# openTPM-v37.net
KiCad netlist of a schematic drawn in EAGLE
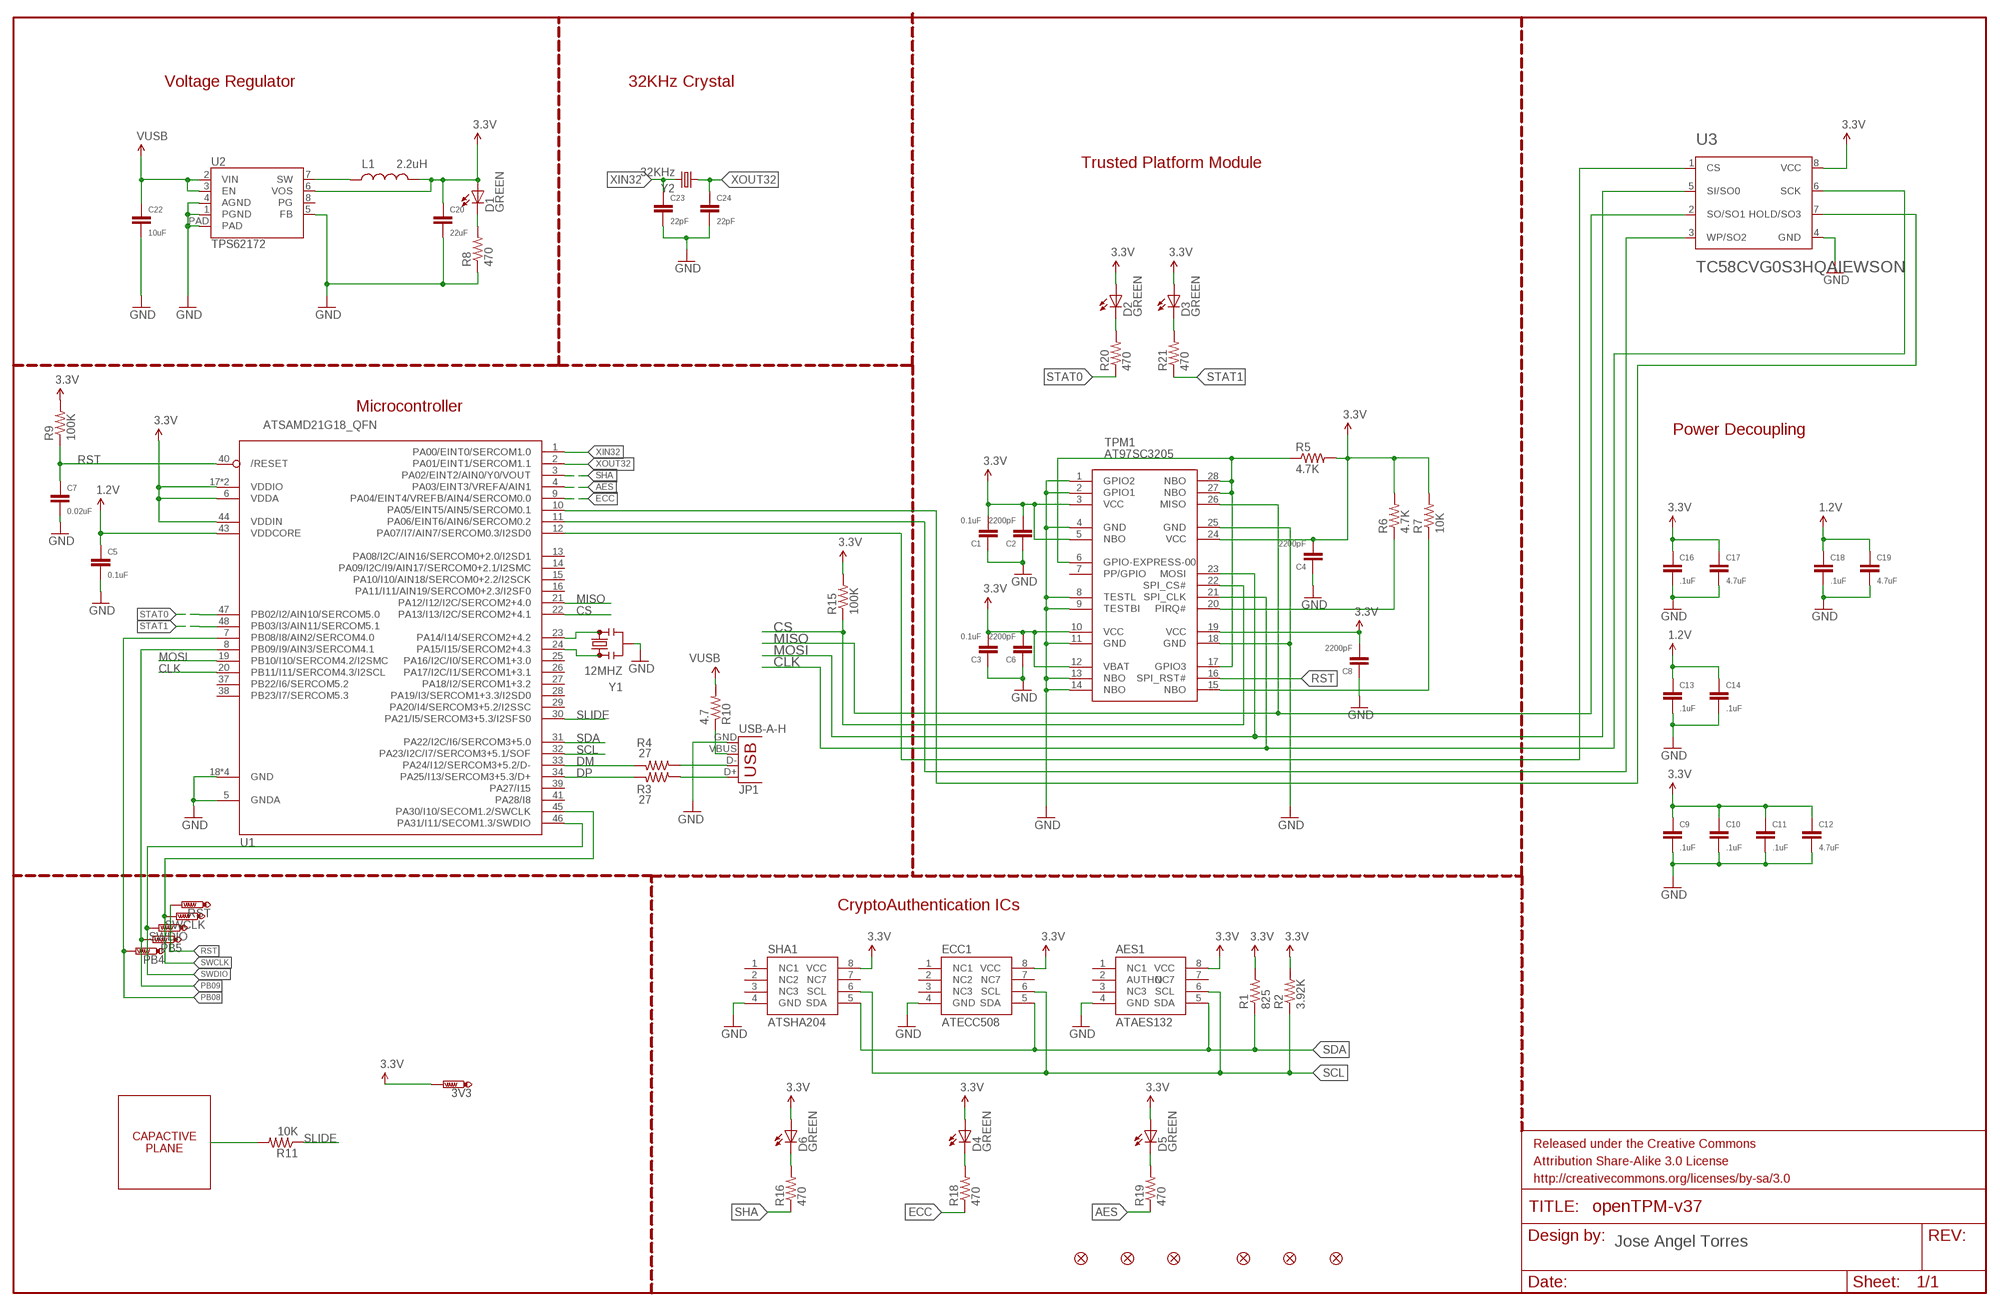
[diagram p0: schematic, sheet 1]

(export (version "E")
  (design (tool "Eeschema 10.0.6"))
  (components
    (comp (ref "3V3")
      (value "PTR1B1,27")
      (footprint "eagle-import:B1,27")
      (libsource (lib "eagle-import") (part "PTR1B1,27"))
    )
    (comp (ref "AES1")
      (value "ATAES132")
      (footprint "eagle-import:CRYPTOTRONIX_SOIC8")
      (libsource (lib "eagle-import") (part "CRYPTOTRONIX_ATAES132"))
    )
    (comp (ref "C1")
      (value "0.1uF")
      (footprint "eagle-import:0402")
      (libsource (lib "eagle-import") (part "CAPACITOR.0402"))
    )
    (comp (ref "C2")
      (value "2200pF")
      (footprint "eagle-import:0402")
      (libsource (lib "eagle-import") (part "CAPACITOR.0402"))
    )
    (comp (ref "C3")
      (value "0.1uF")
      (footprint "eagle-import:0402")
      (libsource (lib "eagle-import") (part "CAPACITOR.0402"))
    )
    (comp (ref "C4")
      (value "2200pF")
      (footprint "eagle-import:0402")
      (libsource (lib "eagle-import") (part "CAPACITOR.0402"))
    )
    (comp (ref "C5")
      (value "0.1uF")
      (footprint "eagle-import:0402")
      (libsource (lib "eagle-import") (part "CAPACITOR.0402"))
    )
    (comp (ref "C6")
      (value "2200pF")
      (footprint "eagle-import:0402")
      (libsource (lib "eagle-import") (part "CAPACITOR.0402"))
    )
    (comp (ref "C7")
      (value "0.02uF")
      (footprint "eagle-import:0402")
      (libsource (lib "eagle-import") (part "CAPACITOR.0402"))
    )
    (comp (ref "C8")
      (value "2200pF")
      (footprint "eagle-import:0402")
      (libsource (lib "eagle-import") (part "CAPACITOR.0402"))
    )
    (comp (ref "C9")
      (value ".1uF")
      (footprint "eagle-import:0402")
      (libsource (lib "eagle-import") (part "CAPACITOR.0402"))
    )
    (comp (ref "C10")
      (value ".1uF")
      (footprint "eagle-import:0402")
      (libsource (lib "eagle-import") (part "CAPACITOR.0402"))
    )
    (comp (ref "C11")
      (value ".1uF")
      (footprint "eagle-import:0402")
      (libsource (lib "eagle-import") (part "CAPACITOR.0402"))
    )
    (comp (ref "C12")
      (value "4.7uF")
      (footprint "eagle-import:0402")
      (libsource (lib "eagle-import") (part "CAPACITOR.0402"))
    )
    (comp (ref "C13")
      (value ".1uF")
      (footprint "eagle-import:0402")
      (libsource (lib "eagle-import") (part "CAPACITOR.0402"))
    )
    (comp (ref "C14")
      (value ".1uF")
      (footprint "eagle-import:0402")
      (libsource (lib "eagle-import") (part "CAPACITOR.0402"))
    )
    (comp (ref "C16")
      (value ".1uF")
      (footprint "eagle-import:0402")
      (libsource (lib "eagle-import") (part "CAPACITOR.0402"))
    )
    (comp (ref "C17")
      (value "4.7uF")
      (footprint "eagle-import:0402")
      (libsource (lib "eagle-import") (part "CAPACITOR.0402"))
    )
    (comp (ref "C18")
      (value ".1uF")
      (footprint "eagle-import:0402")
      (libsource (lib "eagle-import") (part "CAPACITOR.0402"))
    )
    (comp (ref "C19")
      (value "4.7uF")
      (footprint "eagle-import:0402")
      (libsource (lib "eagle-import") (part "CAPACITOR.0402"))
    )
    (comp (ref "C20")
      (value "22uF")
      (footprint "eagle-import:0603")
      (libsource (lib "eagle-import") (part "CAPACITOR.0603"))
    )
    (comp (ref "C22")
      (value "10uF")
      (footprint "eagle-import:0402")
      (libsource (lib "eagle-import") (part "CAPACITOR.0402"))
    )
    (comp (ref "C23")
      (value "22pF")
      (footprint "eagle-import:0402")
      (libsource (lib "eagle-import") (part "CAPACITOR.0402"))
    )
    (comp (ref "C24")
      (value "22pF")
      (footprint "eagle-import:0402")
      (libsource (lib "eagle-import") (part "CAPACITOR.0402"))
    )
    (comp (ref "D1")
      (value "GREEN")
      (footprint "eagle-import:SPARKFUN-LED_LED-0603")
      (libsource (lib "eagle-import") (part "SPARKFUN-LED_LED-GREEN0603"))
    )
    (comp (ref "D2")
      (value "GREEN")
      (footprint "eagle-import:SPARKFUN-LED_LED-0603")
      (libsource (lib "eagle-import") (part "SPARKFUN-LED_LED-GREEN0603"))
    )
    (comp (ref "D3")
      (value "GREEN")
      (footprint "eagle-import:SPARKFUN-LED_LED-0603")
      (libsource (lib "eagle-import") (part "SPARKFUN-LED_LED-GREEN0603"))
    )
    (comp (ref "D4")
      (value "GREEN")
      (footprint "eagle-import:SPARKFUN-LED_LED-0603")
      (libsource (lib "eagle-import") (part "SPARKFUN-LED_LED-GREEN0603"))
    )
    (comp (ref "D5")
      (value "GREEN")
      (footprint "eagle-import:SPARKFUN-LED_LED-0603")
      (libsource (lib "eagle-import") (part "SPARKFUN-LED_LED-GREEN0603"))
    )
    (comp (ref "D6")
      (value "GREEN")
      (footprint "eagle-import:SPARKFUN-LED_LED-0603")
      (libsource (lib "eagle-import") (part "SPARKFUN-LED_LED-GREEN0603"))
    )
    (comp (ref "ECC1")
      (value "ATECC508")
      (footprint "eagle-import:CRYPTOTRONIX_SOIC8")
      (libsource (lib "eagle-import") (part "ATECC508"))
    )
    (comp (ref "FID1")
      (value "SPARKFUN-AESTHETICS_FIDUCIAL1X2")
      (footprint "eagle-import:SPARKFUN-AESTHETICS_FIDUCIAL-1X2")
      (libsource (lib "eagle-import") (part "SPARKFUN-AESTHETICS_FIDUCIAL1X2"))
    )
    (comp (ref "FID2")
      (value "SPARKFUN-AESTHETICS_FIDUCIAL1X2")
      (footprint "eagle-import:SPARKFUN-AESTHETICS_FIDUCIAL-1X2")
      (libsource (lib "eagle-import") (part "SPARKFUN-AESTHETICS_FIDUCIAL1X2"))
    )
    (comp (ref "FID3")
      (value "SPARKFUN-AESTHETICS_FIDUCIAL1X2")
      (footprint "eagle-import:SPARKFUN-AESTHETICS_FIDUCIAL-1X2")
      (libsource (lib "eagle-import") (part "SPARKFUN-AESTHETICS_FIDUCIAL1X2"))
    )
    (comp (ref "FID4")
      (value "SPARKFUN-AESTHETICS_FIDUCIAL1X2")
      (footprint "eagle-import:SPARKFUN-AESTHETICS_FIDUCIAL-1X2")
      (libsource (lib "eagle-import") (part "SPARKFUN-AESTHETICS_FIDUCIAL1X2"))
    )
    (comp (ref "FID5")
      (value "SPARKFUN-AESTHETICS_FIDUCIAL1X2")
      (footprint "eagle-import:SPARKFUN-AESTHETICS_FIDUCIAL-1X2")
      (libsource (lib "eagle-import") (part "SPARKFUN-AESTHETICS_FIDUCIAL1X2"))
    )
    (comp (ref "FID6")
      (value "SPARKFUN-AESTHETICS_FIDUCIAL1X2")
      (footprint "eagle-import:SPARKFUN-AESTHETICS_FIDUCIAL-1X2")
      (libsource (lib "eagle-import") (part "SPARKFUN-AESTHETICS_FIDUCIAL1X2"))
    )
    (comp (ref "JP1")
      (value "USB-A-H")
      (footprint "eagle-import:USB-A-H")
      (libsource (lib "eagle-import") (part "USB-A-H"))
    )
    (comp (ref "L1")
      (value "2.2uH")
      (footprint "eagle-import:C0402")
      (libsource (lib "eagle-import") (part "INDUCTOR0402"))
    )
    (comp (ref "PB4")
      (value "PTR1B1,27")
      (footprint "eagle-import:B1,27")
      (libsource (lib "eagle-import") (part "PTR1B1,27"))
    )
    (comp (ref "PB5")
      (value "PTR1B1,27")
      (footprint "eagle-import:B1,27")
      (libsource (lib "eagle-import") (part "PTR1B1,27"))
    )
    (comp (ref "R1")
      (value "825")
      (footprint "eagle-import:0402")
      (libsource (lib "eagle-import") (part "RESISTOR.0402"))
    )
    (comp (ref "R2")
      (value "3.92K")
      (footprint "eagle-import:0402")
      (libsource (lib "eagle-import") (part "RESISTOR.0402"))
    )
    (comp (ref "R3")
      (value "27")
      (footprint "eagle-import:0402")
      (libsource (lib "eagle-import") (part "RESISTOR.0402"))
    )
    (comp (ref "R4")
      (value "27")
      (footprint "eagle-import:0402")
      (libsource (lib "eagle-import") (part "RESISTOR.0402"))
    )
    (comp (ref "R5")
      (value "4.7K")
      (footprint "eagle-import:0402")
      (libsource (lib "eagle-import") (part "RESISTOR.0402"))
    )
    (comp (ref "R6")
      (value "4.7K")
      (footprint "eagle-import:0402")
      (libsource (lib "eagle-import") (part "RESISTOR.0402"))
    )
    (comp (ref "R7")
      (value "10K")
      (footprint "eagle-import:0402")
      (libsource (lib "eagle-import") (part "RESISTOR.0402"))
    )
    (comp (ref "R8")
      (value "470")
      (footprint "eagle-import:0402")
      (libsource (lib "eagle-import") (part "RESISTOR.0402"))
    )
    (comp (ref "R9")
      (value "100K")
      (footprint "eagle-import:0402")
      (libsource (lib "eagle-import") (part "RESISTOR.0402"))
    )
    (comp (ref "R10")
      (value "4.7")
      (footprint "eagle-import:0402")
      (libsource (lib "eagle-import") (part "RESISTOR.0402"))
    )
    (comp (ref "R11")
      (value "10K")
      (footprint "eagle-import:0402")
      (libsource (lib "eagle-import") (part "RESISTOR.0402"))
    )
    (comp (ref "R15")
      (value "100K")
      (footprint "eagle-import:0402")
      (libsource (lib "eagle-import") (part "RESISTOR.0402"))
    )
    (comp (ref "R16")
      (value "470")
      (footprint "eagle-import:0402")
      (libsource (lib "eagle-import") (part "RESISTOR.0402"))
    )
    (comp (ref "R18")
      (value "470")
      (footprint "eagle-import:0402")
      (libsource (lib "eagle-import") (part "RESISTOR.0402"))
    )
    (comp (ref "R19")
      (value "470")
      (footprint "eagle-import:0402")
      (libsource (lib "eagle-import") (part "RESISTOR.0402"))
    )
    (comp (ref "R20")
      (value "470")
      (footprint "eagle-import:0402")
      (libsource (lib "eagle-import") (part "RESISTOR.0402"))
    )
    (comp (ref "R21")
      (value "470")
      (footprint "eagle-import:0402")
      (libsource (lib "eagle-import") (part "RESISTOR.0402"))
    )
    (comp (ref "RST")
      (value "PTR1B1,27")
      (footprint "eagle-import:B1,27")
      (libsource (lib "eagle-import") (part "PTR1B1,27"))
    )
    (comp (ref "SHA1")
      (value "ATSHA204")
      (footprint "eagle-import:CRYPTOTRONIX_SOIC8")
      (libsource (lib "eagle-import") (part "CRYPTOTRONIX_ATSHA204"))
    )
    (comp (ref "SWCLK")
      (value "PTR1B1,27")
      (footprint "eagle-import:B1,27")
      (libsource (lib "eagle-import") (part "PTR1B1,27"))
    )
    (comp (ref "SWDIO")
      (value "PTR1B1,27")
      (footprint "eagle-import:B1,27")
      (libsource (lib "eagle-import") (part "PTR1B1,27"))
    )
    (comp (ref "TPM1")
      (value "AT97SC3205")
      (footprint "eagle-import:TSSOP28")
      (libsource (lib "eagle-import") (part "AT97SC3205"))
    )
    (comp (ref "U1")
      (value "ATSAMD21G18_QFN")
      (footprint "eagle-import:TQFN48_7MM")
      (libsource (lib "eagle-import") (part "ATSAMD21G_QFN"))
    )
    (comp (ref "U2")
      (value "TPS62172")
      (footprint "eagle-import:WSON-8-PAD")
      (libsource (lib "eagle-import") (part "TPS62172"))
    )
    (comp (ref "U3")
      (value "TC58CVG0S3HQAIEWSON")
      (footprint "eagle-import:WSON-8-PAD")
      (libsource (lib "eagle-import") (part "TC58CVG0S3HQAIEWSON"))
    )
    (comp (ref "Y1")
      (value "12MHZ")
      (footprint "eagle-import:RESONATOR-SMD")
      (libsource (lib "eagle-import") (part "RESONATOR12MHZ"))
    )
    (comp (ref "Y2")
      (value "32KHz")
      (footprint "eagle-import:CRYSTAL-32KHZ-SMD_EPSON_MC146")
      (libsource (lib "eagle-import") (part "CRYSTALEPSONMC146"))
    )
  )
  (nets
    (net (code "1") (name "/CLK") (class "Default")
      (node (ref "TPM1") (pin "21") (pinfunction "SPI_CLK_21") (pintype "bidirectional"))
      (node (ref "U1") (pin "20") (pinfunction "PB11/I11/SERCOM4.3/I2SCL_20") (pintype "bidirectional"))
      (node (ref "U3") (pin "6") (pinfunction "SCK_6") (pintype "bidirectional"))
    )
    (net (code "2") (name "/CS") (class "Default")
      (node (ref "R15") (pin "1") (pinfunction "1_1") (pintype "passive"))
      (node (ref "TPM1") (pin "22") (pinfunction "SPI_CS#_22") (pintype "power_in"))
      (node (ref "U1") (pin "22") (pinfunction "PA13/I13/I2C/SERCOM2+4.1_22") (pintype "bidirectional"))
    )
    (net (code "3") (name "/DM") (class "Default")
      (node (ref "R4") (pin "2") (pinfunction "2_2") (pintype "passive"))
      (node (ref "U1") (pin "33") (pinfunction "PA24/I12/SERCOM3+5.2/D-_33") (pintype "bidirectional"))
    )
    (net (code "4") (name "/DP") (class "Default")
      (node (ref "R3") (pin "2") (pinfunction "2_2") (pintype "passive"))
      (node (ref "U1") (pin "34") (pinfunction "PA25/I13/SERCOM3+5.3/D+_34") (pintype "bidirectional"))
    )
    (net (code "5") (name "/MISO") (class "Default")
      (node (ref "TPM1") (pin "26") (pinfunction "MISO_26") (pintype "power_in"))
      (node (ref "U1") (pin "21") (pinfunction "PA12/I12/I2C/SERCOM2+4.0_21") (pintype "bidirectional"))
      (node (ref "U3") (pin "2") (pinfunction "SO/SO1_2") (pintype "bidirectional"))
    )
    (net (code "6") (name "/MOSI") (class "Default")
      (node (ref "TPM1") (pin "23") (pinfunction "MOSI_23") (pintype "power_in"))
      (node (ref "U1") (pin "19") (pinfunction "PB10/I10/SERCOM4.2/I2SMC_19") (pintype "bidirectional"))
      (node (ref "U3") (pin "5") (pinfunction "SI/SO0_5") (pintype "bidirectional"))
    )
    (net (code "7") (name "/SLIDE") (class "Default")
      (node (ref "R11") (pin "1") (pinfunction "1_1") (pintype "passive"))
      (node (ref "U1") (pin "30") (pinfunction "PA21/I5/SERCOM3+5.3/I2SFS0_30") (pintype "bidirectional"))
    )
    (net (code "8") (name "1.2V") (class "Default")
      (node (ref "C13") (pin "1") (pinfunction "1_1") (pintype "passive"))
      (node (ref "C14") (pin "1") (pinfunction "1_1") (pintype "passive"))
      (node (ref "C18") (pin "1") (pinfunction "1_1") (pintype "passive"))
      (node (ref "C19") (pin "1") (pinfunction "1_1") (pintype "passive"))
      (node (ref "C5") (pin "1") (pinfunction "1_1") (pintype "passive"))
      (node (ref "U1") (pin "43") (pinfunction "VDDCORE_43") (pintype "power_in"))
    )
    (net (code "9") (name "3.3V") (class "Default")
      (node (ref "3V3") (pin "TP") (pinfunction "TP_TP") (pintype "input"))
      (node (ref "AES1") (pin "8") (pinfunction "VCC_8") (pintype "power_in"))
      (node (ref "C1") (pin "2") (pinfunction "2_2") (pintype "passive"))
      (node (ref "C10") (pin "1") (pinfunction "1_1") (pintype "passive"))
      (node (ref "C11") (pin "1") (pinfunction "1_1") (pintype "passive"))
      (node (ref "C12") (pin "1") (pinfunction "1_1") (pintype "passive"))
      (node (ref "C16") (pin "1") (pinfunction "1_1") (pintype "passive"))
      (node (ref "C17") (pin "1") (pinfunction "1_1") (pintype "passive"))
      (node (ref "C2") (pin "2") (pinfunction "2_2") (pintype "passive"))
      (node (ref "C20") (pin "1") (pinfunction "1_1") (pintype "passive"))
      (node (ref "C3") (pin "2") (pinfunction "2_2") (pintype "passive"))
      (node (ref "C4") (pin "2") (pinfunction "2_2") (pintype "passive"))
      (node (ref "C6") (pin "2") (pinfunction "2_2") (pintype "passive"))
      (node (ref "C8") (pin "2") (pinfunction "2_2") (pintype "passive"))
      (node (ref "C9") (pin "1") (pinfunction "1_1") (pintype "passive"))
      (node (ref "D1") (pin "A") (pinfunction "A_A") (pintype "passive"))
      (node (ref "D2") (pin "A") (pinfunction "A_A") (pintype "passive"))
      (node (ref "D3") (pin "A") (pinfunction "A_A") (pintype "passive"))
      (node (ref "D4") (pin "A") (pinfunction "A_A") (pintype "passive"))
      (node (ref "D5") (pin "A") (pinfunction "A_A") (pintype "passive"))
      (node (ref "D6") (pin "A") (pinfunction "A_A") (pintype "passive"))
      (node (ref "ECC1") (pin "8") (pinfunction "VCC_8") (pintype "power_in"))
      (node (ref "L1") (pin "2") (pinfunction "2_2") (pintype "passive"))
      (node (ref "R1") (pin "2") (pinfunction "2_2") (pintype "passive"))
      (node (ref "R15") (pin "2") (pinfunction "2_2") (pintype "passive"))
      (node (ref "R2") (pin "2") (pinfunction "2_2") (pintype "passive"))
      (node (ref "R5") (pin "2") (pinfunction "2_2") (pintype "passive"))
      (node (ref "R6") (pin "2") (pinfunction "2_2") (pintype "passive"))
      (node (ref "R7") (pin "2") (pinfunction "2_2") (pintype "passive"))
      (node (ref "R9") (pin "2") (pinfunction "2_2") (pintype "passive"))
      (node (ref "SHA1") (pin "8") (pinfunction "VCC_8") (pintype "power_in"))
      (node (ref "TPM1") (pin "10") (pinfunction "VCC_10") (pintype "power_in"))
      (node (ref "TPM1") (pin "12") (pinfunction "VBAT_12") (pintype "bidirectional"))
      (node (ref "TPM1") (pin "19") (pinfunction "VCC_19") (pintype "power_in"))
      (node (ref "TPM1") (pin "24") (pinfunction "VCC_24") (pintype "power_in"))
      (node (ref "TPM1") (pin "3") (pinfunction "VCC_3") (pintype "power_in"))
      (node (ref "TPM1") (pin "5") (pinfunction "NBO_5") (pintype "bidirectional"))
      (node (ref "U1") (pin "17") (pinfunction "VDDIO_17") (pintype "power_in"))
      (node (ref "U1") (pin "36") (pinfunction "VDDIO_36") (pintype "power_in"))
      (node (ref "U1") (pin "44") (pinfunction "VDDIN_44") (pintype "power_in"))
      (node (ref "U1") (pin "6") (pinfunction "VDDA_6") (pintype "power_in"))
      (node (ref "U2") (pin "6") (pinfunction "VOS_6") (pintype "bidirectional"))
      (node (ref "U3") (pin "8") (pinfunction "VCC_8") (pintype "bidirectional"))
    )
    (net (code "10") (name "AES") (class "Default")
      (node (ref "R19") (pin "1") (pinfunction "1_1") (pintype "passive"))
      (node (ref "U1") (pin "4") (pinfunction "PA03/EINT3/VREFA/AIN1_4") (pintype "bidirectional"))
    )
    (net (code "11") (name "ECC") (class "Default")
      (node (ref "R18") (pin "1") (pinfunction "1_1") (pintype "passive"))
      (node (ref "U1") (pin "9") (pinfunction "PA04/EINT4/VREFB/AIN4/SERCOM0.0_9") (pintype "bidirectional"))
    )
    (net (code "12") (name "GND") (class "Default")
      (node (ref "AES1") (pin "4") (pinfunction "GND_4") (pintype "power_in"))
      (node (ref "C1") (pin "1") (pinfunction "1_1") (pintype "passive"))
      (node (ref "C10") (pin "2") (pinfunction "2_2") (pintype "passive"))
      (node (ref "C11") (pin "2") (pinfunction "2_2") (pintype "passive"))
      (node (ref "C12") (pin "2") (pinfunction "2_2") (pintype "passive"))
      (node (ref "C13") (pin "2") (pinfunction "2_2") (pintype "passive"))
      (node (ref "C14") (pin "2") (pinfunction "2_2") (pintype "passive"))
      (node (ref "C16") (pin "2") (pinfunction "2_2") (pintype "passive"))
      (node (ref "C17") (pin "2") (pinfunction "2_2") (pintype "passive"))
      (node (ref "C18") (pin "2") (pinfunction "2_2") (pintype "passive"))
      (node (ref "C19") (pin "2") (pinfunction "2_2") (pintype "passive"))
      (node (ref "C2") (pin "1") (pinfunction "1_1") (pintype "passive"))
      (node (ref "C20") (pin "2") (pinfunction "2_2") (pintype "passive"))
      (node (ref "C22") (pin "2") (pinfunction "2_2") (pintype "passive"))
      (node (ref "C23") (pin "2") (pinfunction "2_2") (pintype "passive"))
      (node (ref "C24") (pin "2") (pinfunction "2_2") (pintype "passive"))
      (node (ref "C3") (pin "1") (pinfunction "1_1") (pintype "passive"))
      (node (ref "C4") (pin "1") (pinfunction "1_1") (pintype "passive"))
      (node (ref "C5") (pin "2") (pinfunction "2_2") (pintype "passive"))
      (node (ref "C6") (pin "1") (pinfunction "1_1") (pintype "passive"))
      (node (ref "C7") (pin "2") (pinfunction "2_2") (pintype "passive"))
      (node (ref "C8") (pin "1") (pinfunction "1_1") (pintype "passive"))
      (node (ref "C9") (pin "2") (pinfunction "2_2") (pintype "passive"))
      (node (ref "ECC1") (pin "4") (pinfunction "GND_4") (pintype "power_in"))
      (node (ref "JP1") (pin "GND") (pinfunction "GND_GND") (pintype "bidirectional"))
      (node (ref "R8") (pin "1") (pinfunction "1_1") (pintype "passive"))
      (node (ref "SHA1") (pin "4") (pinfunction "GND_4") (pintype "power_in"))
      (node (ref "TPM1") (pin "1") (pinfunction "GPIO2_1") (pintype "bidirectional"))
      (node (ref "TPM1") (pin "11") (pinfunction "GND_11") (pintype "power_in"))
      (node (ref "TPM1") (pin "13") (pinfunction "NBO_13") (pintype "bidirectional"))
      (node (ref "TPM1") (pin "14") (pinfunction "NBO_14") (pintype "bidirectional"))
      (node (ref "TPM1") (pin "18") (pinfunction "GND_18") (pintype "power_in"))
      (node (ref "TPM1") (pin "2") (pinfunction "GPIO1_2") (pintype "bidirectional"))
      (node (ref "TPM1") (pin "25") (pinfunction "GND_25") (pintype "power_in"))
      (node (ref "TPM1") (pin "4") (pinfunction "GND_4") (pintype "power_in"))
      (node (ref "TPM1") (pin "8") (pinfunction "TESTL_8") (pintype "bidirectional"))
      (node (ref "TPM1") (pin "9") (pinfunction "TESTBI_9") (pintype "bidirectional"))
      (node (ref "U1") (pin "18") (pinfunction "GND_18") (pintype "power_in"))
      (node (ref "U1") (pin "35") (pinfunction "GND_35") (pintype "power_in"))
      (node (ref "U1") (pin "42") (pinfunction "GND_42") (pintype "power_in"))
      (node (ref "U1") (pin "5") (pinfunction "GNDA_5") (pintype "power_in"))
      (node (ref "U1") (pin "THERMAL") (pinfunction "GND_THERMAL") (pintype "power_in"))
      (node (ref "U2") (pin "1") (pinfunction "PGND_1") (pintype "bidirectional"))
      (node (ref "U2") (pin "4") (pinfunction "AGND_4") (pintype "bidirectional"))
      (node (ref "U2") (pin "5") (pinfunction "FB_5") (pintype "bidirectional"))
      (node (ref "U2") (pin "PAD") (pinfunction "PAD_PAD") (pintype "bidirectional"))
      (node (ref "U3") (pin "4") (pinfunction "GND_4") (pintype "bidirectional"))
      (node (ref "Y1") (pin "2") (pinfunction "2_2") (pintype "passive"))
    )
    (net (code "13") (name "Net-(D1-PadC)") (class "Default")
      (node (ref "D1") (pin "C") (pinfunction "C_C") (pintype "passive"))
      (node (ref "R8") (pin "2") (pinfunction "2_2") (pintype "passive"))
    )
    (net (code "14") (name "Net-(D2-PadC)") (class "Default")
      (node (ref "D2") (pin "C") (pinfunction "C_C") (pintype "passive"))
      (node (ref "R20") (pin "2") (pinfunction "2_2") (pintype "passive"))
    )
    (net (code "15") (name "Net-(D3-PadC)") (class "Default")
      (node (ref "D3") (pin "C") (pinfunction "C_C") (pintype "passive"))
      (node (ref "R21") (pin "2") (pinfunction "2_2") (pintype "passive"))
    )
    (net (code "16") (name "Net-(D4-PadC)") (class "Default")
      (node (ref "D4") (pin "C") (pinfunction "C_C") (pintype "passive"))
      (node (ref "R18") (pin "2") (pinfunction "2_2") (pintype "passive"))
    )
    (net (code "17") (name "Net-(D5-PadC)") (class "Default")
      (node (ref "D5") (pin "C") (pinfunction "C_C") (pintype "passive"))
      (node (ref "R19") (pin "2") (pinfunction "2_2") (pintype "passive"))
    )
    (net (code "18") (name "Net-(D6-PadC)") (class "Default")
      (node (ref "D6") (pin "C") (pinfunction "C_C") (pintype "passive"))
      (node (ref "R16") (pin "2") (pinfunction "2_2") (pintype "passive"))
    )
    (net (code "19") (name "Net-(JP1-PadD+)") (class "Default")
      (node (ref "JP1") (pin "D+") (pinfunction "D+_D+") (pintype "bidirectional"))
      (node (ref "R3") (pin "1") (pinfunction "1_1") (pintype "passive"))
    )
    (net (code "20") (name "Net-(JP1-PadD-)") (class "Default")
      (node (ref "JP1") (pin "D-") (pinfunction "D-_D-") (pintype "bidirectional"))
      (node (ref "R4") (pin "1") (pinfunction "1_1") (pintype "passive"))
    )
    (net (code "21") (name "Net-(JP1-PadVBUS)") (class "Default")
      (node (ref "JP1") (pin "VBUS") (pinfunction "VBUS_VBUS") (pintype "bidirectional"))
      (node (ref "R10") (pin "1") (pinfunction "1_1") (pintype "passive"))
    )
    (net (code "22") (name "Net-(R7-Pad1)") (class "Default")
      (node (ref "R7") (pin "1") (pinfunction "1_1") (pintype "passive"))
      (node (ref "TPM1") (pin "15") (pinfunction "NBO_15") (pintype "bidirectional"))
    )
    (net (code "23") (name "Net-(TPM1-GPIO-EXPRESS-00)") (class "Default")
      (node (ref "R5") (pin "1") (pinfunction "1_1") (pintype "passive"))
      (node (ref "TPM1") (pin "17") (pinfunction "GPIO3_17") (pintype "power_in"))
      (node (ref "TPM1") (pin "27") (pinfunction "NBO_27") (pintype "bidirectional"))
      (node (ref "TPM1") (pin "28") (pinfunction "NBO_28") (pintype "bidirectional"))
      (node (ref "TPM1") (pin "6") (pinfunction "GPIO-EXPRESS-00_6") (pintype "power_in"))
    )
    (net (code "24") (name "Net-(TPM1-PIRQ#)") (class "Default")
      (node (ref "R6") (pin "1") (pinfunction "1_1") (pintype "passive"))
      (node (ref "TPM1") (pin "20") (pinfunction "PIRQ#_20") (pintype "power_in"))
    )
    (net (code "25") (name "Net-(U1-PA05{slash}EINT5{slash}AIN5{slash}SERCOM0.1)") (class "Default")
      (node (ref "U1") (pin "10") (pinfunction "PA05/EINT5/AIN5/SERCOM0.1_10") (pintype "bidirectional"))
      (node (ref "U3") (pin "7") (pinfunction "HOLD/SO3_7") (pintype "bidirectional"))
    )
    (net (code "26") (name "Net-(U1-PA06{slash}EINT6{slash}AIN6{slash}SERCOM0.2)") (class "Default")
      (node (ref "U1") (pin "11") (pinfunction "PA06/EINT6/AIN6/SERCOM0.2_11") (pintype "bidirectional"))
      (node (ref "U3") (pin "3") (pinfunction "WP/SO2_3") (pintype "bidirectional"))
    )
    (net (code "27") (name "Net-(U1-PA07{slash}I7{slash}AIN7{slash}SERCOM0.3{slash}I2SD0)") (class "Default")
      (node (ref "U1") (pin "12") (pinfunction "PA07/I7/AIN7/SERCOM0.3/I2SD0_12") (pintype "bidirectional"))
      (node (ref "U3") (pin "1") (pinfunction "CS_1") (pintype "bidirectional"))
    )
    (net (code "28") (name "Net-(U1-PA14{slash}I14{slash}SERCOM2+4.2)") (class "Default")
      (node (ref "U1") (pin "23") (pinfunction "PA14/I14/SERCOM2+4.2_23") (pintype "bidirectional"))
      (node (ref "Y1") (pin "3") (pinfunction "3_3") (pintype "passive"))
    )
    (net (code "29") (name "Net-(U1-PA15{slash}I15{slash}SERCOM2+4.3)") (class "Default")
      (node (ref "U1") (pin "24") (pinfunction "PA15/I15/SERCOM2+4.3_24") (pintype "bidirectional"))
      (node (ref "Y1") (pin "1") (pinfunction "1_1") (pintype "passive"))
    )
    (net (code "30") (name "Net-(U2-SW)") (class "Default")
      (node (ref "L1") (pin "1") (pinfunction "1_1") (pintype "passive"))
      (node (ref "U2") (pin "7") (pinfunction "SW_7") (pintype "bidirectional"))
    )
    (net (code "31") (name "PB08") (class "Default")
      (node (ref "PB4") (pin "TP") (pinfunction "TP_TP") (pintype "input"))
      (node (ref "U1") (pin "7") (pinfunction "PB08/I8/AIN2/SERCOM4.0_7") (pintype "bidirectional"))
    )
    (net (code "32") (name "PB09") (class "Default")
      (node (ref "PB5") (pin "TP") (pinfunction "TP_TP") (pintype "input"))
      (node (ref "U1") (pin "8") (pinfunction "PB09/I9/AIN3/SERCOM4.1_8") (pintype "bidirectional"))
    )
    (net (code "33") (name "RST") (class "Default")
      (node (ref "C7") (pin "1") (pinfunction "1_1") (pintype "passive"))
      (node (ref "R9") (pin "1") (pinfunction "1_1") (pintype "passive"))
      (node (ref "RST") (pin "TP") (pinfunction "TP_TP") (pintype "input"))
      (node (ref "TPM1") (pin "16") (pinfunction "SPI_RST#_16") (pintype "bidirectional"))
      (node (ref "U1") (pin "40") (pinfunction "/RESET_40") (pintype "bidirectional"))
    )
    (net (code "34") (name "SCL") (class "Default")
      (node (ref "AES1") (pin "6") (pinfunction "SCL_6") (pintype "bidirectional"))
      (node (ref "ECC1") (pin "6") (pinfunction "SCL_6") (pintype "bidirectional"))
      (node (ref "R2") (pin "1") (pinfunction "1_1") (pintype "passive"))
      (node (ref "SHA1") (pin "6") (pinfunction "SCL_6") (pintype "bidirectional"))
      (node (ref "U1") (pin "32") (pinfunction "PA23/I2C/I7/SERCOM3+5.1/SOF_32") (pintype "bidirectional"))
    )
    (net (code "35") (name "SDA") (class "Default")
      (node (ref "AES1") (pin "5") (pinfunction "SDA_5") (pintype "bidirectional"))
      (node (ref "ECC1") (pin "5") (pinfunction "SDA_5") (pintype "bidirectional"))
      (node (ref "R1") (pin "1") (pinfunction "1_1") (pintype "passive"))
      (node (ref "SHA1") (pin "5") (pinfunction "SDA_5") (pintype "bidirectional"))
      (node (ref "U1") (pin "31") (pinfunction "PA22/I2C/I6/SERCOM3+5.0_31") (pintype "bidirectional"))
    )
    (net (code "36") (name "SHA") (class "Default")
      (node (ref "R16") (pin "1") (pinfunction "1_1") (pintype "passive"))
      (node (ref "U1") (pin "3") (pinfunction "PA02/EINT2/AIN0/Y0/VOUT_3") (pintype "bidirectional"))
    )
    (net (code "37") (name "STAT0") (class "Default")
      (node (ref "R20") (pin "1") (pinfunction "1_1") (pintype "passive"))
      (node (ref "U1") (pin "47") (pinfunction "PB02/I2/AIN10/SERCOM5.0_47") (pintype "bidirectional"))
    )
    (net (code "38") (name "STAT1") (class "Default")
      (node (ref "R21") (pin "1") (pinfunction "1_1") (pintype "passive"))
      (node (ref "U1") (pin "48") (pinfunction "PB03/I3/AIN11/SERCOM5.1_48") (pintype "bidirectional"))
    )
    (net (code "39") (name "SWCLK") (class "Default")
      (node (ref "SWCLK") (pin "TP") (pinfunction "TP_TP") (pintype "input"))
      (node (ref "U1") (pin "45") (pinfunction "PA30/I10/SECOM1.2/SWCLK_45") (pintype "bidirectional"))
    )
    (net (code "40") (name "SWDIO") (class "Default")
      (node (ref "SWDIO") (pin "TP") (pinfunction "TP_TP") (pintype "input"))
      (node (ref "U1") (pin "46") (pinfunction "PA31/I11/SECOM1.3/SWDIO_46") (pintype "bidirectional"))
    )
    (net (code "41") (name "VUSB") (class "Default")
      (node (ref "C22") (pin "1") (pinfunction "1_1") (pintype "passive"))
      (node (ref "R10") (pin "2") (pinfunction "2_2") (pintype "passive"))
      (node (ref "U2") (pin "2") (pinfunction "VIN_2") (pintype "bidirectional"))
      (node (ref "U2") (pin "3") (pinfunction "EN_3") (pintype "bidirectional"))
    )
    (net (code "42") (name "XIN32") (class "Default")
      (node (ref "C23") (pin "1") (pinfunction "1_1") (pintype "passive"))
      (node (ref "U1") (pin "1") (pinfunction "PA00/EINT0/SERCOM1.0_1") (pintype "bidirectional"))
      (node (ref "Y2") (pin "P$1") (pinfunction "2_P$1") (pintype "passive"))
    )
    (net (code "43") (name "XOUT32") (class "Default")
      (node (ref "C24") (pin "1") (pinfunction "1_1") (pintype "passive"))
      (node (ref "U1") (pin "2") (pinfunction "PA01/EINT1/SERCOM1.1_2") (pintype "bidirectional"))
      (node (ref "Y2") (pin "P$2") (pinfunction "1_P$2") (pintype "passive"))
    )
    (net (code "44") (name "unconnected-(AES1-AUTHO-Pad2)") (class "Default")
      (node (ref "AES1") (pin "2") (pinfunction "AUTHO_2") (pintype "bidirectional"))
    )
    (net (code "45") (name "unconnected-(AES1-NC1-Pad1)") (class "Default")
      (node (ref "AES1") (pin "1") (pinfunction "NC1_1") (pintype "no_connect"))
    )
    (net (code "46") (name "unconnected-(AES1-NC3-Pad3)") (class "Default")
      (node (ref "AES1") (pin "3") (pinfunction "NC3_3") (pintype "no_connect"))
    )
    (net (code "47") (name "unconnected-(AES1-NC7-Pad7)") (class "Default")
      (node (ref "AES1") (pin "7") (pinfunction "NC7_7") (pintype "no_connect"))
    )
    (net (code "48") (name "unconnected-(ECC1-NC1-Pad1)") (class "Default")
      (node (ref "ECC1") (pin "1") (pinfunction "NC1_1") (pintype "bidirectional"))
    )
    (net (code "49") (name "unconnected-(ECC1-NC2-Pad2)") (class "Default")
      (node (ref "ECC1") (pin "2") (pinfunction "NC2_2") (pintype "no_connect"))
    )
    (net (code "50") (name "unconnected-(ECC1-NC3-Pad3)") (class "Default")
      (node (ref "ECC1") (pin "3") (pinfunction "NC3_3") (pintype "no_connect"))
    )
    (net (code "51") (name "unconnected-(ECC1-NC7-Pad7)") (class "Default")
      (node (ref "ECC1") (pin "7") (pinfunction "NC7_7") (pintype "no_connect"))
    )
    (net (code "52") (name "unconnected-(R11-Pad2)") (class "Default")
      (node (ref "R11") (pin "2") (pinfunction "2_2") (pintype "passive"))
    )
    (net (code "53") (name "unconnected-(SHA1-NC1-Pad1)") (class "Default")
      (node (ref "SHA1") (pin "1") (pinfunction "NC1_1") (pintype "no_connect"))
    )
    (net (code "54") (name "unconnected-(SHA1-NC2-Pad2)") (class "Default")
      (node (ref "SHA1") (pin "2") (pinfunction "NC2_2") (pintype "no_connect"))
    )
    (net (code "55") (name "unconnected-(SHA1-NC3-Pad3)") (class "Default")
      (node (ref "SHA1") (pin "3") (pinfunction "NC3_3") (pintype "no_connect"))
    )
    (net (code "56") (name "unconnected-(SHA1-NC7-Pad7)") (class "Default")
      (node (ref "SHA1") (pin "7") (pinfunction "NC7_7") (pintype "no_connect"))
    )
    (net (code "57") (name "unconnected-(TPM1-PP{slash}GPIO-Pad7)") (class "Default")
      (node (ref "TPM1") (pin "7") (pinfunction "PP/GPIO_7") (pintype "bidirectional"))
    )
    (net (code "58") (name "unconnected-(U1-PA08{slash}I2C{slash}AIN16{slash}SERCOM0+2.0{slash}I2SD1-Pad13)") (class "Default")
      (node (ref "U1") (pin "13") (pinfunction "PA08/I2C/AIN16/SERCOM0+2.0/I2SD1_13") (pintype "bidirectional"))
    )
    (net (code "59") (name "unconnected-(U1-PA09{slash}I2C{slash}I9{slash}AIN17{slash}SERCOM0+2.1{slash}I2SMC-Pad14)") (class "Default")
      (node (ref "U1") (pin "14") (pinfunction "PA09/I2C/I9/AIN17/SERCOM0+2.1/I2SMC_14") (pintype "bidirectional"))
    )
    (net (code "60") (name "unconnected-(U1-PA10{slash}I10{slash}AIN18{slash}SERCOM0+2.2{slash}I2SCK-Pad15)") (class "Default")
      (node (ref "U1") (pin "15") (pinfunction "PA10/I10/AIN18/SERCOM0+2.2/I2SCK_15") (pintype "bidirectional"))
    )
    (net (code "61") (name "unconnected-(U1-PA11{slash}I11{slash}AIN19{slash}SERCOM0+2.3{slash}I2SF0-Pad16)") (class "Default")
      (node (ref "U1") (pin "16") (pinfunction "PA11/I11/AIN19/SERCOM0+2.3/I2SF0_16") (pintype "bidirectional"))
    )
    (net (code "62") (name "unconnected-(U1-PA16{slash}I2C{slash}I0{slash}SERCOM1+3.0-Pad25)") (class "Default")
      (node (ref "U1") (pin "25") (pinfunction "PA16/I2C/I0/SERCOM1+3.0_25") (pintype "bidirectional"))
    )
    (net (code "63") (name "unconnected-(U1-PA17{slash}I2C{slash}I1{slash}SERCOM1+3.1-Pad26)") (class "Default")
      (node (ref "U1") (pin "26") (pinfunction "PA17/I2C/I1/SERCOM1+3.1_26") (pintype "bidirectional"))
    )
    (net (code "64") (name "unconnected-(U1-PA18{slash}I2{slash}SERCOM1+3.2-Pad27)") (class "Default")
      (node (ref "U1") (pin "27") (pinfunction "PA18/I2/SERCOM1+3.2_27") (pintype "bidirectional"))
    )
    (net (code "65") (name "unconnected-(U1-PA19{slash}I3{slash}SERCOM1+3.3{slash}I2SD0-Pad28)") (class "Default")
      (node (ref "U1") (pin "28") (pinfunction "PA19/I3/SERCOM1+3.3/I2SD0_28") (pintype "bidirectional"))
    )
    (net (code "66") (name "unconnected-(U1-PA20{slash}I4{slash}SERCOM3+5.2{slash}I2SSC-Pad29)") (class "Default")
      (node (ref "U1") (pin "29") (pinfunction "PA20/I4/SERCOM3+5.2/I2SSC_29") (pintype "bidirectional"))
    )
    (net (code "67") (name "unconnected-(U1-PA27{slash}I15-Pad39)") (class "Default")
      (node (ref "U1") (pin "39") (pinfunction "PA27/I15_39") (pintype "bidirectional"))
    )
    (net (code "68") (name "unconnected-(U1-PA28{slash}I8-Pad41)") (class "Default")
      (node (ref "U1") (pin "41") (pinfunction "PA28/I8_41") (pintype "bidirectional"))
    )
    (net (code "69") (name "unconnected-(U1-PB22{slash}I6{slash}SERCOM5.2-Pad37)") (class "Default")
      (node (ref "U1") (pin "37") (pinfunction "PB22/I6/SERCOM5.2_37") (pintype "bidirectional"))
    )
    (net (code "70") (name "unconnected-(U1-PB23{slash}I7{slash}SERCOM5.3-Pad38)") (class "Default")
      (node (ref "U1") (pin "38") (pinfunction "PB23/I7/SERCOM5.3_38") (pintype "bidirectional"))
    )
    (net (code "71") (name "unconnected-(U2-PG-Pad8)") (class "Default")
      (node (ref "U2") (pin "8") (pinfunction "PG_8") (pintype "bidirectional"))
    )
  )
)
